# powersupply.net
KiCad netlist of a schematic drawn in EAGLE
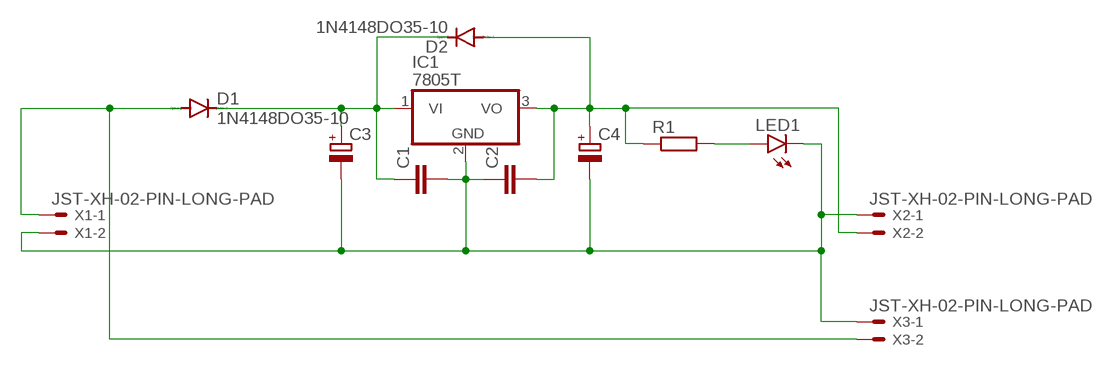
[diagram p0: schematic, sheet 1]

(export (version "E")
  (design (tool "Eeschema 10.0.6"))
  (components
    (comp (ref "C1")
      (value "C-EU025-024X044")
      (footprint "eagle-import:C025-024X044")
      (libsource (lib "eagle-import") (part "C-EU025-024X044"))
    )
    (comp (ref "C2")
      (value "C-EU025-024X044")
      (footprint "eagle-import:C025-024X044")
      (libsource (lib "eagle-import") (part "C-EU025-024X044"))
    )
    (comp (ref "C3")
      (value "CPOL-EUE2,5-6E")
      (footprint "eagle-import:E2,5-6E")
      (libsource (lib "eagle-import") (part "CPOL-EUE2,5-6E"))
    )
    (comp (ref "C4")
      (value "CPOL-EUE2,5-6E")
      (footprint "eagle-import:E2,5-6E")
      (libsource (lib "eagle-import") (part "CPOL-EUE2,5-6E"))
    )
    (comp (ref "D1")
      (value "1N4148DO35-10")
      (footprint "eagle-import:DO35-10")
      (libsource (lib "eagle-import") (part "1N4148DO35-10"))
    )
    (comp (ref "D2")
      (value "1N4148DO35-10")
      (footprint "eagle-import:DO35-10")
      (libsource (lib "eagle-import") (part "1N4148DO35-10"))
    )
    (comp (ref "IC1")
      (value "7805T")
      (footprint "eagle-import:TO220H")
      (libsource (lib "eagle-import") (part "78T05"))
    )
    (comp (ref "LED1")
      (value "LED5MM")
      (footprint "eagle-import:LED5MM")
      (libsource (lib "eagle-import") (part "LED5MM"))
    )
    (comp (ref "R1")
      (value "R-EU_0207/10")
      (footprint "eagle-import:0207_10")
      (libsource (lib "eagle-import") (part "R-EU_0207/10"))
    )
    (comp (ref "X1")
      (value "JST-XH-02-PIN-LONG-PAD")
      (footprint "eagle-import:JST-XH-02-PACKAGE-LONG-PAD")
      (libsource (lib "eagle-import") (part "JST-XH-02-PIN-LONG-PAD"))
    )
    (comp (ref "X2")
      (value "JST-XH-02-PIN-LONG-PAD")
      (footprint "eagle-import:JST-XH-02-PACKAGE-LONG-PAD")
      (libsource (lib "eagle-import") (part "JST-XH-02-PIN-LONG-PAD"))
    )
    (comp (ref "X3")
      (value "JST-XH-02-PIN-LONG-PAD")
      (footprint "eagle-import:JST-XH-02-PACKAGE-LONG-PAD")
      (libsource (lib "eagle-import") (part "JST-XH-02-PIN-LONG-PAD"))
    )
  )
  (nets
    (net (code "1") (name "Net-(IC1-GND)") (class "Default")
      (node (ref "C1") (pin "2") (pinfunction "2_2") (pintype "passive"))
      (node (ref "C2") (pin "1") (pinfunction "1_1") (pintype "passive"))
      (node (ref "C3") (pin "-") (pinfunction "-_-") (pintype "passive"))
      (node (ref "C4") (pin "-") (pinfunction "-_-") (pintype "passive"))
      (node (ref "IC1") (pin "2") (pinfunction "GND_2") (pintype "passive"))
      (node (ref "LED1") (pin "K") (pinfunction "C_K") (pintype "passive"))
      (node (ref "X1") (pin "2") (pinfunction "S_2") (pintype "passive"))
      (node (ref "X2") (pin "1") (pinfunction "S_1") (pintype "passive"))
      (node (ref "X3") (pin "1") (pinfunction "S_1") (pintype "passive"))
    )
    (net (code "2") (name "Net-(IC1-VI)") (class "Default")
      (node (ref "C1") (pin "1") (pinfunction "1_1") (pintype "passive"))
      (node (ref "C3") (pin "+") (pinfunction "+_+") (pintype "passive"))
      (node (ref "D1") (pin "C") (pinfunction "C_C") (pintype "passive"))
      (node (ref "D2") (pin "C") (pinfunction "C_C") (pintype "passive"))
      (node (ref "IC1") (pin "1") (pinfunction "VI_1") (pintype "input"))
    )
    (net (code "3") (name "Net-(IC1-VO)") (class "Default")
      (node (ref "C2") (pin "2") (pinfunction "2_2") (pintype "passive"))
      (node (ref "C4") (pin "+") (pinfunction "+_+") (pintype "passive"))
      (node (ref "D2") (pin "A") (pinfunction "A_A") (pintype "passive"))
      (node (ref "IC1") (pin "3") (pinfunction "VO_3") (pintype "passive"))
      (node (ref "R1") (pin "1") (pinfunction "1_1") (pintype "passive"))
      (node (ref "X2") (pin "2") (pinfunction "S_2") (pintype "passive"))
    )
    (net (code "4") (name "Net-(LED1-PadA)") (class "Default")
      (node (ref "LED1") (pin "A") (pinfunction "A_A") (pintype "passive"))
      (node (ref "R1") (pin "2") (pinfunction "2_2") (pintype "passive"))
    )
    (net (code "5") (name "Net-(X1A-S)") (class "Default")
      (node (ref "D1") (pin "A") (pinfunction "A_A") (pintype "passive"))
      (node (ref "X1") (pin "1") (pinfunction "S_1") (pintype "passive"))
      (node (ref "X3") (pin "2") (pinfunction "S_2") (pintype "passive"))
    )
  )
)
